# USB_HS_PHY.net
KiCad netlist of a schematic drawn in Altium Designer
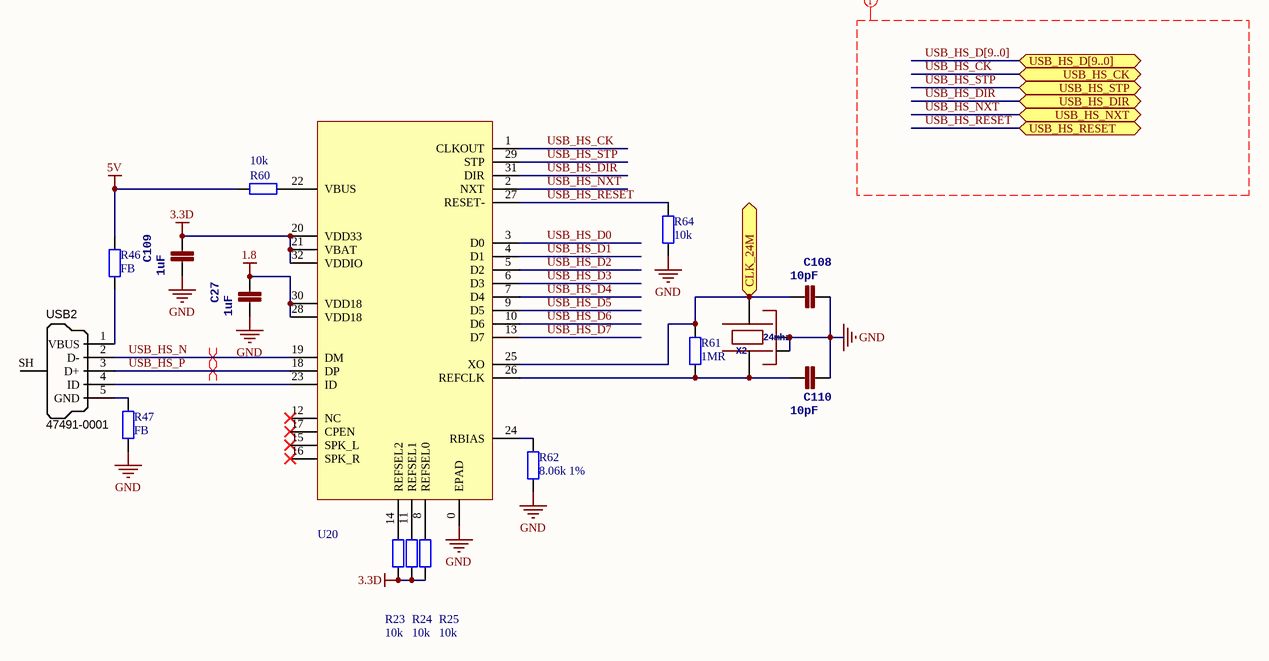
[diagram p0: USB_HS_PHY.SchDoc]

(export (version "E")
  (design (tool "Eeschema 10.0.6"))
  (components
    (comp (ref "C27")
      (value "1uF")
      (footprint "0402")
      (description "<b>Capacitor</b>\nStandard 0603 ceramic capacitor, and 0.1\" leaded capacitor.")
      (fields (field (name "PARTNO") "CC0402ZRY5V7BB104"))
      (libsource (lib "pixhawk2") (part "CAP0402-CAP"))
    )
    (comp (ref "C108")
      (value "10pF")
      (footprint "0402")
      (description "<b>Capacitor</b>\nStandard 0603 ceramic capacitor, and 0.1\" leaded capacitor.")
      (fields (field (name "PARTNO") "CC0402ZRY5V7BB104"))
      (libsource (lib "") (part "CAP0402-CAP_1"))
    )
    (comp (ref "C109")
      (value "1uF")
      (footprint "0402")
      (description "<b>Capacitor</b>\nStandard 0603 ceramic capacitor, and 0.1\" leaded capacitor.")
      (fields (field (name "PARTNO") "CC0402ZRY5V7BB104"))
      (libsource (lib "pixhawk2") (part "CAP0402-CAP"))
    )
    (comp (ref "C110")
      (value "10pF")
      (footprint "0402")
      (description "<b>Capacitor</b>\nStandard 0603 ceramic capacitor, and 0.1\" leaded capacitor.")
      (fields (field (name "PARTNO") "CC0402ZRY5V7BB104"))
      (libsource (lib "*") (part "CAP0402-CAP"))
    )
    (comp (ref "R23")
      (value "10k")
      (footprint "0402")
      (description "Resistor")
      (fields (field (name "PUBLISHER") "Altium Limited"))
      (libsource (lib "Miscellaneous Devices") (part "Res2"))
    )
    (comp (ref "R24")
      (value "10k")
      (footprint "0402")
      (description "Resistor")
      (fields (field (name "PUBLISHER") "Altium Limited"))
      (libsource (lib "Miscellaneous Devices") (part "Res2"))
    )
    (comp (ref "R25")
      (value "10k")
      (footprint "0402")
      (description "Resistor")
      (fields (field (name "PUBLISHER") "Altium Limited"))
      (libsource (lib "Miscellaneous Devices") (part "Res2"))
    )
    (comp (ref "R46")
      (value "FB")
      (footprint "0603")
      (description "Resistor")
      (fields (field (name "PUBLISHER") "Altium Limited"))
      (libsource (lib "Miscellaneous Devices") (part "Res2"))
    )
    (comp (ref "R47")
      (value "FB")
      (footprint "0603")
      (description "Resistor")
      (fields (field (name "PUBLISHER") "Altium Limited"))
      (libsource (lib "Miscellaneous Devices") (part "Res2"))
    )
    (comp (ref "R60")
      (value "10k")
      (footprint "0402")
      (description "Resistor")
      (fields (field (name "PUBLISHER") "Altium Limited"))
      (libsource (lib "") (part "Res2_2"))
    )
    (comp (ref "R61")
      (value "1MR")
      (footprint "0402")
      (description "Resistor")
      (fields (field (name "PUBLISHER") "Altium Limited"))
      (libsource (lib "") (part "Res2_1"))
    )
    (comp (ref "R62")
      (value "8.06k 1%")
      (footprint "0402")
      (description "Resistor")
      (fields (field (name "PUBLISHER") "Altium Limited"))
      (libsource (lib "") (part "Res2_1"))
    )
    (comp (ref "R64")
      (value "10k")
      (footprint "0402")
      (description "Resistor")
      (fields (field (name "PUBLISHER") "Altium Limited"))
      (libsource (lib "Miscellaneous Devices") (part "Res2"))
    )
    (comp (ref "U20") (value "USB3320") (footprint "USB3300") (libsource (lib "F4SDR") (part "USB3320")))
    (comp (ref "USB2")
      (value "USB Micro Type B")
      (footprint "MICRO-YZX")
      (description "Connector SMD USB Micro Type B middle mount")
      (fields (field (name "MANUFACTURER PART NUMBER 1") "47491-0001"))
      (libsource (lib "PBL - Connectors") (part "USB_Micro_TypeB"))
    )
    (comp (ref "X2")
      (value "24mhz")
      (footprint "OSCILLATOR-3.2X2.5")
      (description "Crystal Oscillator in 3.2x2.5 SMD")
      (libsource (lib "sch") (part "OSCILLATOR-3.2X2.5"))
    )
  )
  (nets
    (net (code "3") (name "/CLK_24M") (class "Default")
      (node (ref "C108") (pin "2") (pinfunction "2_2") (pintype "passive"))
      (node (ref "R61") (pin "2") (pinfunction "2_2") (pintype "passive"))
      (node (ref "U20") (pin "25") (pinfunction "XO_25") (pintype "passive"))
      (node (ref "X2") (pin "3") (pinfunction "3_3") (pintype "passive"))
    )
    (net (code "4") (name "/USB_HS_CK") (class "Default")
      (node (ref "U20") (pin "1") (pinfunction "CLKOUT_1") (pintype "passive"))
    )
    (net (code "5") (name "/USB_HS_D0") (class "Default")
      (node (ref "U20") (pin "3") (pinfunction "D0_3") (pintype "passive"))
    )
    (net (code "6") (name "/USB_HS_D1") (class "Default")
      (node (ref "U20") (pin "4") (pinfunction "D1_4") (pintype "passive"))
    )
    (net (code "7") (name "/USB_HS_D2") (class "Default")
      (node (ref "U20") (pin "5") (pinfunction "D2_5") (pintype "passive"))
    )
    (net (code "8") (name "/USB_HS_D3") (class "Default")
      (node (ref "U20") (pin "6") (pinfunction "D3_6") (pintype "passive"))
    )
    (net (code "9") (name "/USB_HS_D4") (class "Default")
      (node (ref "U20") (pin "7") (pinfunction "D4_7") (pintype "passive"))
    )
    (net (code "10") (name "/USB_HS_D5") (class "Default")
      (node (ref "U20") (pin "9") (pinfunction "D5_9") (pintype "passive"))
    )
    (net (code "11") (name "/USB_HS_D6") (class "Default")
      (node (ref "U20") (pin "10") (pinfunction "D6_10") (pintype "passive"))
    )
    (net (code "12") (name "/USB_HS_D7") (class "Default")
      (node (ref "U20") (pin "13") (pinfunction "D7_13") (pintype "passive"))
    )
    (net (code "13") (name "/USB_HS_DIR") (class "Default")
      (node (ref "U20") (pin "31") (pinfunction "DIR_31") (pintype "passive"))
    )
    (net (code "15") (name "/USB_HS_N") (class "Default")
      (node (ref "U20") (pin "19") (pinfunction "DM_19") (pintype "passive"))
      (node (ref "USB2") (pin "2") (pinfunction "D-_2") (pintype "passive"))
    )
    (net (code "16") (name "/USB_HS_NXT") (class "Default")
      (node (ref "U20") (pin "2") (pinfunction "NXT_2") (pintype "passive"))
    )
    (net (code "17") (name "/USB_HS_P") (class "Default")
      (node (ref "U20") (pin "18") (pinfunction "DP_18") (pintype "passive"))
      (node (ref "USB2") (pin "3") (pinfunction "D+_3") (pintype "passive"))
    )
    (net (code "18") (name "/USB_HS_RESET") (class "Default")
      (node (ref "R64") (pin "1") (pinfunction "1_1") (pintype "passive"))
      (node (ref "U20") (pin "27") (pinfunction "RESET-_27") (pintype "passive"))
    )
    (net (code "19") (name "/USB_HS_STP") (class "Default")
      (node (ref "U20") (pin "29") (pinfunction "STP_29") (pintype "passive"))
    )
    (net (code "20") (name "1.8") (class "Default")
      (node (ref "C27") (pin "1") (pinfunction "1_1") (pintype "passive"))
      (node (ref "U20") (pin "28") (pinfunction "VDD18_28") (pintype "passive"))
      (node (ref "U20") (pin "30") (pinfunction "VDD18_30") (pintype "passive"))
    )
    (net (code "21") (name "3.3D") (class "Default")
      (node (ref "C109") (pin "1") (pinfunction "1_1") (pintype "passive"))
      (node (ref "R23") (pin "2") (pinfunction "2_2") (pintype "passive"))
      (node (ref "R24") (pin "2") (pinfunction "2_2") (pintype "passive"))
      (node (ref "R25") (pin "2") (pinfunction "2_2") (pintype "passive"))
      (node (ref "U20") (pin "20") (pinfunction "VDD33_20") (pintype "passive"))
      (node (ref "U20") (pin "21") (pinfunction "VBAT_21") (pintype "passive"))
      (node (ref "U20") (pin "32") (pinfunction "VDDIO_32") (pintype "passive"))
    )
    (net (code "22") (name "5V") (class "Default")
      (node (ref "R46") (pin "1") (pinfunction "1_1") (pintype "passive"))
      (node (ref "R60") (pin "1") (pinfunction "1_1") (pintype "passive"))
    )
    (net (code "23") (name "GND") (class "Default")
      (node (ref "C108") (pin "1") (pinfunction "1_1") (pintype "passive"))
      (node (ref "C109") (pin "2") (pinfunction "2_2") (pintype "passive"))
      (node (ref "C110") (pin "1") (pinfunction "1_1") (pintype "passive"))
      (node (ref "C27") (pin "2") (pinfunction "2_2") (pintype "passive"))
      (node (ref "R47") (pin "2") (pinfunction "2_2") (pintype "passive"))
      (node (ref "R62") (pin "1") (pinfunction "1_1") (pintype "passive"))
      (node (ref "R64") (pin "2") (pinfunction "2_2") (pintype "passive"))
      (node (ref "U20") (pin "0") (pinfunction "EPAD_0") (pintype "passive"))
      (node (ref "X2") (pin "2") (pinfunction "NC_2_2") (pintype "open_emitter"))
      (node (ref "X2") (pin "4") (pinfunction "NC_4_4") (pintype "open_emitter"))
    )
    (net (code "24") (name "Net-(U20-ID)") (class "Default")
      (node (ref "U20") (pin "23") (pinfunction "ID_23") (pintype "passive"))
      (node (ref "USB2") (pin "4") (pinfunction "ID_4") (pintype "passive"))
    )
    (net (code "25") (name "Net-(U20-RBIAS)") (class "Default")
      (node (ref "R62") (pin "2") (pinfunction "2_2") (pintype "passive"))
      (node (ref "U20") (pin "24") (pinfunction "RBIAS_24") (pintype "passive"))
    )
    (net (code "26") (name "Net-(U20-REFCLK)") (class "Default")
      (node (ref "C110") (pin "2") (pinfunction "2_2") (pintype "passive"))
      (node (ref "R61") (pin "1") (pinfunction "1_1") (pintype "passive"))
      (node (ref "U20") (pin "26") (pinfunction "REFCLK_26") (pintype "passive"))
      (node (ref "X2") (pin "1") (pinfunction "1_1") (pintype "passive"))
    )
    (net (code "27") (name "Net-(U20-REFSEL0)") (class "Default")
      (node (ref "R25") (pin "1") (pinfunction "1_1") (pintype "passive"))
      (node (ref "U20") (pin "8") (pinfunction "REFSEL0_8") (pintype "passive"))
    )
    (net (code "28") (name "Net-(U20-REFSEL1)") (class "Default")
      (node (ref "R24") (pin "1") (pinfunction "1_1") (pintype "passive"))
      (node (ref "U20") (pin "11") (pinfunction "REFSEL1_11") (pintype "passive"))
    )
    (net (code "29") (name "Net-(U20-REFSEL2)") (class "Default")
      (node (ref "R23") (pin "1") (pinfunction "1_1") (pintype "passive"))
      (node (ref "U20") (pin "14") (pinfunction "REFSEL2_14") (pintype "passive"))
    )
    (net (code "30") (name "Net-(U20-VBUS)") (class "Default")
      (node (ref "R60") (pin "2") (pinfunction "2_2") (pintype "passive"))
      (node (ref "U20") (pin "22") (pinfunction "VBUS_22") (pintype "passive"))
    )
    (net (code "31") (name "Net-(USB2-GND)") (class "Default")
      (node (ref "R47") (pin "1") (pinfunction "1_1") (pintype "passive"))
      (node (ref "USB2") (pin "5") (pinfunction "GND_5") (pintype "passive"))
    )
    (net (code "32") (name "Net-(USB2-VBUS)") (class "Default")
      (node (ref "R46") (pin "2") (pinfunction "2_2") (pintype "passive"))
      (node (ref "USB2") (pin "1") (pinfunction "VBUS_1") (pintype "passive"))
    )
    (net (code "33") (name "unconnected-(U20-CPEN-Pad17)") (class "Default")
      (node (ref "U20") (pin "17") (pinfunction "CPEN_17") (pintype "passive+no_connect"))
    )
    (net (code "34") (name "unconnected-(U20-NC-Pad12)") (class "Default")
      (node (ref "U20") (pin "12") (pinfunction "NC_12") (pintype "passive+no_connect"))
    )
    (net (code "35") (name "unconnected-(U20-SPK_L-Pad15)") (class "Default")
      (node (ref "U20") (pin "15") (pinfunction "SPK_L_15") (pintype "passive+no_connect"))
    )
    (net (code "36") (name "unconnected-(U20-SPK_R-Pad16)") (class "Default")
      (node (ref "U20") (pin "16") (pinfunction "SPK_R_16") (pintype "passive+no_connect"))
    )
    (net (code "37") (name "unconnected-(USB2-Shell-PadSH)") (class "Default")
      (node (ref "USB2") (pin "SH") (pinfunction "Shell_SH") (pintype "passive"))
    )
  )
)
